# iofresh.net
KiCad netlist of a schematic drawn in EAGLE
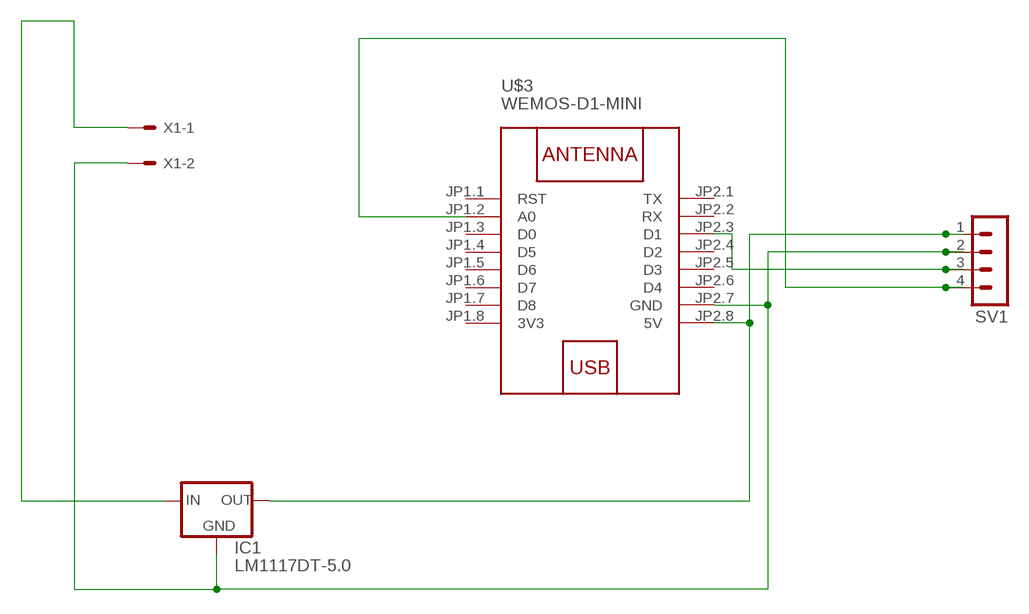
[diagram p0: schematic, sheet 1]

(export (version "E")
  (design (tool "Eeschema 10.0.6"))
  (components
    (comp (ref "IC1")
      (value "LM1117DT-5.0")
      (footprint "eagle-import:TO252")
      (fields (field (name "MF") "Texas Instruments"))
      (libsource (lib "eagle-import") (part "LM1117?-DT5.0"))
    )
    (comp (ref "SV1")
      (value "MA04-1")
      (footprint "eagle-import:MA04-1")
      (libsource (lib "eagle-import") (part "MA04-1"))
    )
    (comp (ref "U$3")
      (value "WEMOS-D1-MINI")
      (footprint "eagle-import:WEMOS-D1-MINI")
      (libsource (lib "eagle-import") (part "WEMOS-D1-MINI"))
    )
    (comp (ref "X1")
      (value "KK-156-2")
      (footprint "eagle-import:KK-156-2")
      (fields (field (name "MF") "MOLEX"))
      (libsource (lib "eagle-import") (part "KK-156-2"))
    )
  )
  (nets
    (net (code "1") (name "/3V3") (class "Default")
      (node (ref "U$3") (pin "JP1.8") (pinfunction "3V3_JP1.8") (pintype "power_in"))
    )
    (net (code "2") (name "Net-(IC1-GND)") (class "Default")
      (node (ref "IC1") (pin "1") (pinfunction "GND_1") (pintype "input"))
      (node (ref "SV1") (pin "2") (pinfunction "2_2") (pintype "passive"))
      (node (ref "U$3") (pin "JP2.7") (pinfunction "GND_JP2.7") (pintype "power_in"))
      (node (ref "X1") (pin "2") (pinfunction "S_2") (pintype "passive"))
    )
    (net (code "3") (name "Net-(IC1-IN)") (class "Default")
      (node (ref "IC1") (pin "2") (pinfunction "IN_2") (pintype "input"))
      (node (ref "X1") (pin "1") (pinfunction "S_1") (pintype "passive"))
    )
    (net (code "4") (name "Net-(IC1-OUT)") (class "Default")
      (node (ref "IC1") (pin "3") (pinfunction "OUT_3") (pintype "passive"))
      (node (ref "SV1") (pin "1") (pinfunction "1_1") (pintype "passive"))
      (node (ref "U$3") (pin "JP2.8") (pinfunction "5V_JP2.8") (pintype "power_in"))
    )
    (net (code "5") (name "Net-(U$3-A0)") (class "Default")
      (node (ref "SV1") (pin "4") (pinfunction "4_4") (pintype "passive"))
      (node (ref "U$3") (pin "JP1.2") (pinfunction "A0_JP1.2") (pintype "bidirectional"))
    )
    (net (code "6") (name "Net-(U$3-D1)") (class "Default")
      (node (ref "SV1") (pin "3") (pinfunction "3_3") (pintype "passive"))
      (node (ref "U$3") (pin "JP2.3") (pinfunction "D1_JP2.3") (pintype "bidirectional"))
    )
    (net (code "7") (name "unconnected-(U$3-D0-PadJP1.3)") (class "Default")
      (node (ref "U$3") (pin "JP1.3") (pinfunction "D0_JP1.3") (pintype "bidirectional"))
    )
    (net (code "8") (name "unconnected-(U$3-D2-PadJP2.4)") (class "Default")
      (node (ref "U$3") (pin "JP2.4") (pinfunction "D2_JP2.4") (pintype "bidirectional"))
    )
    (net (code "9") (name "unconnected-(U$3-D3-PadJP2.5)") (class "Default")
      (node (ref "U$3") (pin "JP2.5") (pinfunction "D3_JP2.5") (pintype "bidirectional"))
    )
    (net (code "10") (name "unconnected-(U$3-D4-PadJP2.6)") (class "Default")
      (node (ref "U$3") (pin "JP2.6") (pinfunction "D4_JP2.6") (pintype "bidirectional"))
    )
    (net (code "11") (name "unconnected-(U$3-D5-PadJP1.4)") (class "Default")
      (node (ref "U$3") (pin "JP1.4") (pinfunction "D5_JP1.4") (pintype "bidirectional"))
    )
    (net (code "12") (name "unconnected-(U$3-D6-PadJP1.5)") (class "Default")
      (node (ref "U$3") (pin "JP1.5") (pinfunction "D6_JP1.5") (pintype "bidirectional"))
    )
    (net (code "13") (name "unconnected-(U$3-D7-PadJP1.6)") (class "Default")
      (node (ref "U$3") (pin "JP1.6") (pinfunction "D7_JP1.6") (pintype "bidirectional"))
    )
    (net (code "14") (name "unconnected-(U$3-D8-PadJP1.7)") (class "Default")
      (node (ref "U$3") (pin "JP1.7") (pinfunction "D8_JP1.7") (pintype "bidirectional"))
    )
    (net (code "15") (name "unconnected-(U$3-RST-PadJP1.1)") (class "Default")
      (node (ref "U$3") (pin "JP1.1") (pinfunction "RST_JP1.1") (pintype "bidirectional"))
    )
    (net (code "16") (name "unconnected-(U$3-RX-PadJP2.2)") (class "Default")
      (node (ref "U$3") (pin "JP2.2") (pinfunction "RX_JP2.2") (pintype "bidirectional"))
    )
    (net (code "17") (name "unconnected-(U$3-TX-PadJP2.1)") (class "Default")
      (node (ref "U$3") (pin "JP2.1") (pinfunction "TX_JP2.1") (pintype "bidirectional"))
    )
  )
)
